# GEX_IDC_rev2.net
KiCad netlist of a schematic drawn in Altium Designer
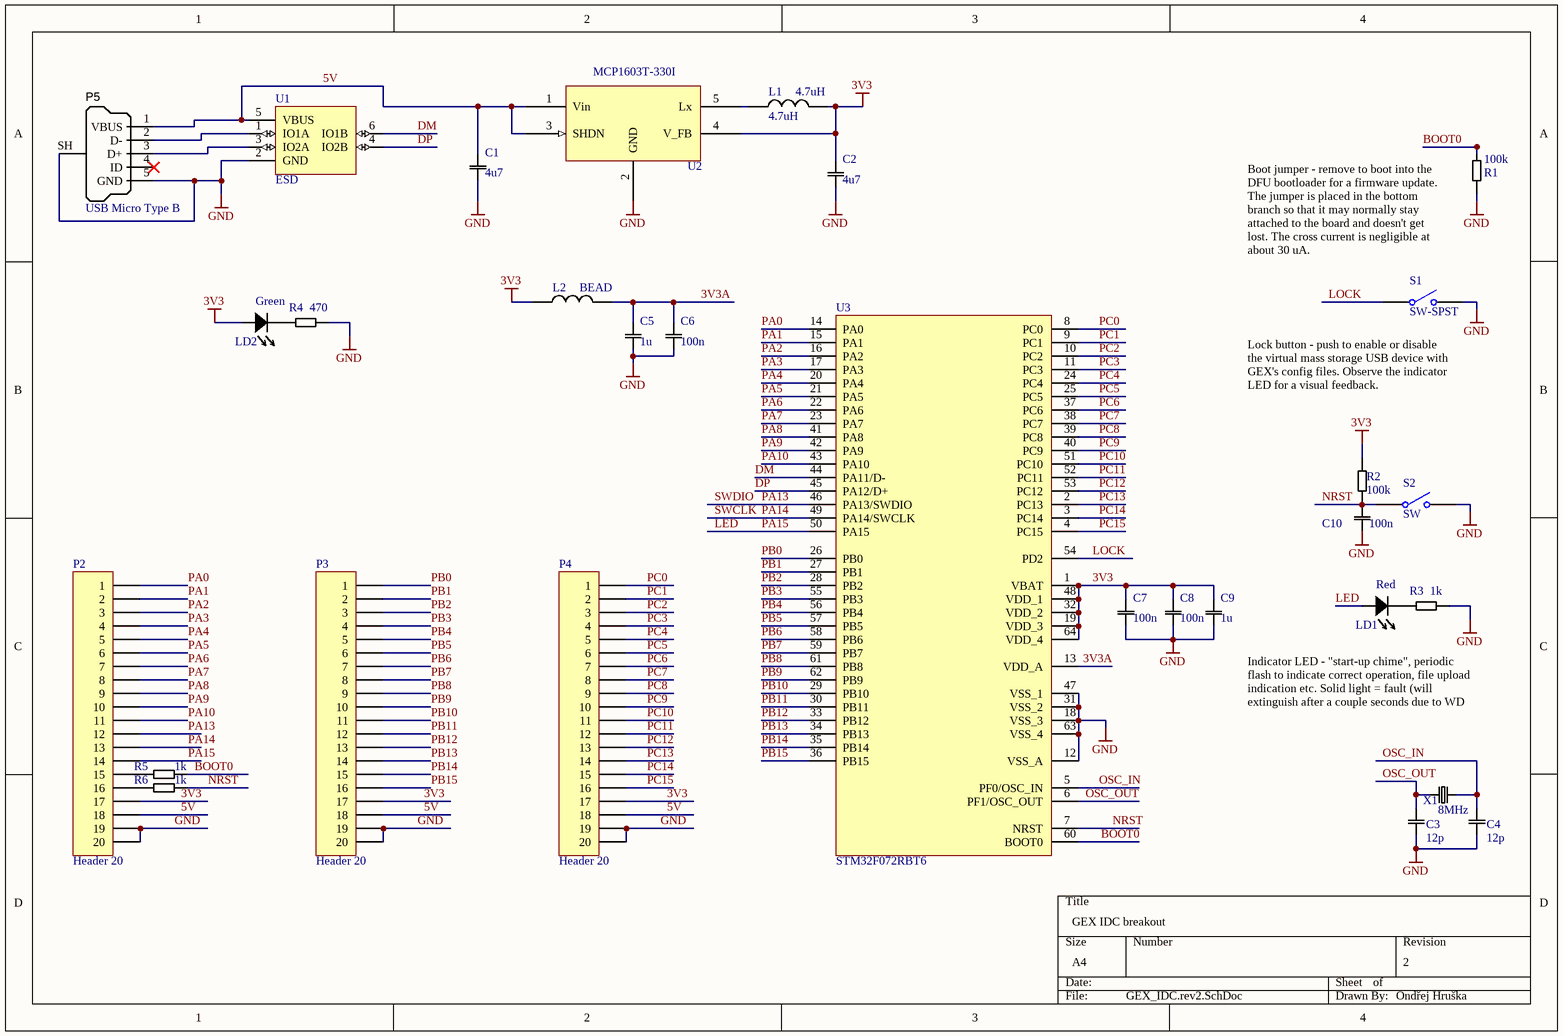
[diagram p0: GEX_IDC.rev2.SchDoc]

(export (version "E")
  (design (tool "Eeschema 10.0.6"))
  (components
    (comp (ref "C1")
      (value "4u7")
      (footprint "ABU_standard:C1206")
      (libsource (lib "ABU_standard") (part "C"))
    )
    (comp (ref "C2")
      (value "4u7")
      (footprint "ABU_standard:C1206")
      (libsource (lib "ABU_standard") (part "C"))
    )
    (comp (ref "C3")
      (value "12p")
      (footprint "ABU_standard:C0805")
      (libsource (lib "ABU_standard") (part "C"))
    )
    (comp (ref "C4")
      (value "12p")
      (footprint "ABU_standard:C0805")
      (libsource (lib "ABU_standard") (part "C"))
    )
    (comp (ref "C5")
      (value "1u")
      (footprint "ABU_standard:C0805")
      (libsource (lib "ABU_standard") (part "C"))
    )
    (comp (ref "C6")
      (value "100n")
      (footprint "ABU_standard:C0805")
      (libsource (lib "ABU_standard") (part "C"))
    )
    (comp (ref "C7")
      (value "100n")
      (footprint "ABU_standard:C0805")
      (libsource (lib "ABU_standard") (part "C"))
    )
    (comp (ref "C8")
      (value "100n")
      (footprint "ABU_standard:C0805")
      (libsource (lib "ABU_standard") (part "C"))
    )
    (comp (ref "C9")
      (value "1u")
      (footprint "ABU_standard:C0805")
      (libsource (lib "ABU_standard") (part "C"))
    )
    (comp (ref "C10")
      (value "100n")
      (footprint "ABU_standard:C0805")
      (libsource (lib "ABU_standard") (part "C"))
    )
    (comp (ref "L1")
      (value "4.7uH")
      (footprint "L_3x3")
      (description "Inductor")
      (fields (field (name "ALTIUM_VALUE") "4.7uH") (field (name "PART NUMBER") "VLS3015ET-4R7M"))
      (libsource (lib "ABU_standard") (part "L"))
    )
    (comp (ref "L2")
      (value "BEAD")
      (footprint "R0805")
      (description "Inductor")
      (libsource (lib "ABU_standard") (part "L"))
    )
    (comp (ref "LD1") (value "Red") (footprint "LED_SMD") (libsource (lib "ABU_standard") (part "LED")))
    (comp (ref "LD2") (value "Green") (footprint "LED_SMD") (libsource (lib "ABU_standard") (part "LED")))
    (comp (ref "P2")
      (value "Header 20")
      (footprint "MLW20_GEX_14")
      (description "Header, 20-Pin")
      (fields (field (name "PUBLISHER") "Altium Limited"))
      (libsource (lib "Miscellaneous Connectors") (part "Header 20"))
    )
    (comp (ref "P3")
      (value "Header 20")
      (footprint "MLW20_GEX_16")
      (description "Header, 20-Pin")
      (fields (field (name "PUBLISHER") "Altium Limited"))
      (libsource (lib "Miscellaneous Connectors") (part "Header 20"))
    )
    (comp (ref "P4")
      (value "Header 20")
      (footprint "MLW20_GEX_16")
      (description "Header, 20-Pin")
      (fields (field (name "PUBLISHER") "Altium Limited"))
      (libsource (lib "Miscellaneous Connectors") (part "Header 20"))
    )
    (comp (ref "P5")
      (value "USB Micro Type B")
      (footprint "USB_Micro-B_AFCI_10118194")
      (description "Connector SMD USB Micro Type B bottom mount, (recommended if hand soldering)")
      (fields (field (name "Comment") "USB_Micro_TypeB_Molex_105017"))
      (libsource (lib "CONN") (part "USB_Micro_TypeB_Molex_105017"))
    )
    (comp (ref "R1") (value "100k") (footprint "R0805") (libsource (lib "") (part "R_1")))
    (comp (ref "R2") (value "100k") (footprint "R0805") (libsource (lib "") (part "R_1")))
    (comp (ref "R3") (value "1k") (footprint "R0805") (libsource (lib "ABU_standard") (part "R")))
    (comp (ref "R4") (value "470") (footprint "R0805") (libsource (lib "ABU_standard") (part "R")))
    (comp (ref "R5") (value "1k") (footprint "R0805") (libsource (lib "ABU_standard") (part "R")))
    (comp (ref "R6") (value "1k") (footprint "R0805") (libsource (lib "ABU_standard") (part "R")))
    (comp (ref "S1")
      (value "SW-SPST")
      (footprint "BTN_AJ050")
      (description "Single-Pole, Single-Throw Switch")
      (fields (field (name "PUBLISHER") "Altium Limited"))
      (libsource (lib "Miscellaneous Devices") (part "SW-SPST"))
    )
    (comp (ref "S2") (value "SW") (footprint "SW_TINY_4PAD") (libsource (lib "CUSTOM") (part "SW_SPST_4PAD")))
    (comp (ref "U1") (value "ESD") (footprint "SOT23-6") (libsource (lib "CUSTOM") (part "USBLC6_ESD")))
    (comp (ref "U2")
      (value "MCP1603T-330I")
      (footprint "SOT23-5")
      (libsource (lib "CUSTOM") (part "MCP1603"))
    )
    (comp (ref "U3")
      (value "STM32F072RBT6")
      (footprint "LQFP64")
      (libsource (lib "CUSTOM") (part "STM32F072RBT6"))
    )
    (comp (ref "X1")
      (value "8MHz")
      (footprint "XTAL-SMD-50-32")
      (libsource (lib "ABU_standard") (part "XTALL"))
    )
  )
  (nets
    (net (code "1") (name "/3V3A") (class "Default")
      (node (ref "C5") (pin "2") (pinfunction "2_2") (pintype "passive"))
      (node (ref "C6") (pin "2") (pinfunction "2_2") (pintype "passive"))
      (node (ref "L2") (pin "2") (pinfunction "2_2") (pintype "passive"))
      (node (ref "U3") (pin "13") (pinfunction "VDD_A_13") (pintype "power_in"))
    )
    (net (code "2") (name "/5V") (class "Default")
      (node (ref "C1") (pin "2") (pinfunction "2_2") (pintype "passive"))
      (node (ref "P2") (pin "18") (pinfunction "18_18") (pintype "passive"))
      (node (ref "P3") (pin "18") (pinfunction "18_18") (pintype "passive"))
      (node (ref "P4") (pin "18") (pinfunction "18_18") (pintype "passive"))
      (node (ref "P5") (pin "1") (pinfunction "VBUS_1") (pintype "passive"))
      (node (ref "U1") (pin "5") (pinfunction "VBUS_5") (pintype "power_in"))
      (node (ref "U2") (pin "1") (pinfunction "Vin_1") (pintype "power_in"))
      (node (ref "U2") (pin "3") (pinfunction "SHDN_3") (pintype "input"))
    )
    (net (code "3") (name "/BOOT0") (class "Default")
      (node (ref "R1") (pin "1") (pinfunction "1_1") (pintype "passive"))
      (node (ref "R5") (pin "1") (pinfunction "1_1") (pintype "passive"))
      (node (ref "U3") (pin "60") (pinfunction "BOOT0_60") (pintype "passive"))
    )
    (net (code "4") (name "/DM") (class "Default")
      (node (ref "U1") (pin "6") (pinfunction "IO1B_6") (pintype "bidirectional"))
      (node (ref "U3") (pin "44") (pinfunction "PA11/D-_44") (pintype "passive"))
    )
    (net (code "5") (name "/DP") (class "Default")
      (node (ref "U1") (pin "4") (pinfunction "IO2B_4") (pintype "bidirectional"))
      (node (ref "U3") (pin "45") (pinfunction "PA12/D+_45") (pintype "passive"))
    )
    (net (code "6") (name "/LED") (class "Default")
      (node (ref "LD1") (pin "A") (pinfunction "A_A") (pintype "passive"))
      (node (ref "P2") (pin "14") (pinfunction "14_14") (pintype "passive"))
      (node (ref "U3") (pin "50") (pinfunction "PA15_50") (pintype "passive"))
    )
    (net (code "7") (name "/LOCK") (class "Default")
      (node (ref "S1") (pin "1") (pinfunction "COMMON_1") (pintype "passive"))
      (node (ref "U3") (pin "54") (pinfunction "PD2_54") (pintype "passive"))
    )
    (net (code "8") (name "/NRST") (class "Default")
      (node (ref "C10") (pin "2") (pinfunction "2_2") (pintype "passive"))
      (node (ref "R2") (pin "2") (pinfunction "2_2") (pintype "passive"))
      (node (ref "R6") (pin "1") (pinfunction "1_1") (pintype "passive"))
      (node (ref "S2") (pin "1") (pinfunction "COMMON_1") (pintype "passive"))
      (node (ref "U3") (pin "7") (pinfunction "NRST_7") (pintype "passive"))
    )
    (net (code "9") (name "/OSC_IN") (class "Default")
      (node (ref "C4") (pin "2") (pinfunction "2_2") (pintype "passive"))
      (node (ref "U3") (pin "5") (pinfunction "PF0/OSC_IN_5") (pintype "passive"))
      (node (ref "X1") (pin "2") (pinfunction "2_2") (pintype "passive"))
    )
    (net (code "10") (name "/OSC_OUT") (class "Default")
      (node (ref "C3") (pin "2") (pinfunction "2_2") (pintype "passive"))
      (node (ref "U3") (pin "6") (pinfunction "PF1/OSC_OUT_6") (pintype "passive"))
      (node (ref "X1") (pin "1") (pinfunction "1_1") (pintype "passive"))
    )
    (net (code "11") (name "/PA0") (class "Default")
      (node (ref "P2") (pin "1") (pinfunction "1_1") (pintype "passive"))
      (node (ref "U3") (pin "14") (pinfunction "PA0_14") (pintype "passive"))
    )
    (net (code "12") (name "/PA1") (class "Default")
      (node (ref "P2") (pin "2") (pinfunction "2_2") (pintype "passive"))
      (node (ref "U3") (pin "15") (pinfunction "PA1_15") (pintype "passive"))
    )
    (net (code "13") (name "/PA2") (class "Default")
      (node (ref "P2") (pin "3") (pinfunction "3_3") (pintype "passive"))
      (node (ref "U3") (pin "16") (pinfunction "PA2_16") (pintype "passive"))
    )
    (net (code "14") (name "/PA3") (class "Default")
      (node (ref "P2") (pin "4") (pinfunction "4_4") (pintype "passive"))
      (node (ref "U3") (pin "17") (pinfunction "PA3_17") (pintype "passive"))
    )
    (net (code "15") (name "/PA4") (class "Default")
      (node (ref "P2") (pin "5") (pinfunction "5_5") (pintype "passive"))
      (node (ref "U3") (pin "20") (pinfunction "PA4_20") (pintype "passive"))
    )
    (net (code "16") (name "/PA5") (class "Default")
      (node (ref "P2") (pin "6") (pinfunction "6_6") (pintype "passive"))
      (node (ref "U3") (pin "21") (pinfunction "PA5_21") (pintype "passive"))
    )
    (net (code "17") (name "/PA6") (class "Default")
      (node (ref "P2") (pin "7") (pinfunction "7_7") (pintype "passive"))
      (node (ref "U3") (pin "22") (pinfunction "PA6_22") (pintype "passive"))
    )
    (net (code "18") (name "/PA7") (class "Default")
      (node (ref "P2") (pin "8") (pinfunction "8_8") (pintype "passive"))
      (node (ref "U3") (pin "23") (pinfunction "PA7_23") (pintype "passive"))
    )
    (net (code "19") (name "/PA8") (class "Default")
      (node (ref "P2") (pin "9") (pinfunction "9_9") (pintype "passive"))
      (node (ref "U3") (pin "41") (pinfunction "PA8_41") (pintype "passive"))
    )
    (net (code "20") (name "/PA9") (class "Default")
      (node (ref "P2") (pin "10") (pinfunction "10_10") (pintype "passive"))
      (node (ref "U3") (pin "42") (pinfunction "PA9_42") (pintype "passive"))
    )
    (net (code "21") (name "/PA10") (class "Default")
      (node (ref "P2") (pin "11") (pinfunction "11_11") (pintype "passive"))
      (node (ref "U3") (pin "43") (pinfunction "PA10_43") (pintype "passive"))
    )
    (net (code "22") (name "/PA13") (class "Default")
      (node (ref "P2") (pin "12") (pinfunction "12_12") (pintype "passive"))
      (node (ref "U3") (pin "46") (pinfunction "PA13/SWDIO_46") (pintype "passive"))
    )
    (net (code "23") (name "/PA14") (class "Default")
      (node (ref "P2") (pin "13") (pinfunction "13_13") (pintype "passive"))
      (node (ref "U3") (pin "49") (pinfunction "PA14/SWCLK_49") (pintype "passive"))
    )
    (net (code "24") (name "/PB0") (class "Default")
      (node (ref "P3") (pin "1") (pinfunction "1_1") (pintype "passive"))
      (node (ref "U3") (pin "26") (pinfunction "PB0_26") (pintype "passive"))
    )
    (net (code "25") (name "/PB1") (class "Default")
      (node (ref "P3") (pin "2") (pinfunction "2_2") (pintype "passive"))
      (node (ref "U3") (pin "27") (pinfunction "PB1_27") (pintype "passive"))
    )
    (net (code "26") (name "/PB2") (class "Default")
      (node (ref "P3") (pin "3") (pinfunction "3_3") (pintype "passive"))
      (node (ref "U3") (pin "28") (pinfunction "PB2_28") (pintype "passive"))
    )
    (net (code "27") (name "/PB3") (class "Default")
      (node (ref "P3") (pin "4") (pinfunction "4_4") (pintype "passive"))
      (node (ref "U3") (pin "55") (pinfunction "PB3_55") (pintype "passive"))
    )
    (net (code "28") (name "/PB4") (class "Default")
      (node (ref "P3") (pin "5") (pinfunction "5_5") (pintype "passive"))
      (node (ref "U3") (pin "56") (pinfunction "PB4_56") (pintype "passive"))
    )
    (net (code "29") (name "/PB5") (class "Default")
      (node (ref "P3") (pin "6") (pinfunction "6_6") (pintype "passive"))
      (node (ref "U3") (pin "57") (pinfunction "PB5_57") (pintype "passive"))
    )
    (net (code "30") (name "/PB6") (class "Default")
      (node (ref "P3") (pin "7") (pinfunction "7_7") (pintype "passive"))
      (node (ref "U3") (pin "58") (pinfunction "PB6_58") (pintype "passive"))
    )
    (net (code "31") (name "/PB7") (class "Default")
      (node (ref "P3") (pin "8") (pinfunction "8_8") (pintype "passive"))
      (node (ref "U3") (pin "59") (pinfunction "PB7_59") (pintype "passive"))
    )
    (net (code "32") (name "/PB8") (class "Default")
      (node (ref "P3") (pin "9") (pinfunction "9_9") (pintype "passive"))
      (node (ref "U3") (pin "61") (pinfunction "PB8_61") (pintype "passive"))
    )
    (net (code "33") (name "/PB9") (class "Default")
      (node (ref "P3") (pin "10") (pinfunction "10_10") (pintype "passive"))
      (node (ref "U3") (pin "62") (pinfunction "PB9_62") (pintype "passive"))
    )
    (net (code "34") (name "/PB10") (class "Default")
      (node (ref "P3") (pin "11") (pinfunction "11_11") (pintype "passive"))
      (node (ref "U3") (pin "29") (pinfunction "PB10_29") (pintype "passive"))
    )
    (net (code "35") (name "/PB11") (class "Default")
      (node (ref "P3") (pin "12") (pinfunction "12_12") (pintype "passive"))
      (node (ref "U3") (pin "30") (pinfunction "PB11_30") (pintype "passive"))
    )
    (net (code "36") (name "/PB12") (class "Default")
      (node (ref "P3") (pin "13") (pinfunction "13_13") (pintype "passive"))
      (node (ref "U3") (pin "33") (pinfunction "PB12_33") (pintype "passive"))
    )
    (net (code "37") (name "/PB13") (class "Default")
      (node (ref "P3") (pin "14") (pinfunction "14_14") (pintype "passive"))
      (node (ref "U3") (pin "34") (pinfunction "PB13_34") (pintype "passive"))
    )
    (net (code "38") (name "/PB14") (class "Default")
      (node (ref "P3") (pin "15") (pinfunction "15_15") (pintype "passive"))
      (node (ref "U3") (pin "35") (pinfunction "PB14_35") (pintype "passive"))
    )
    (net (code "39") (name "/PB15") (class "Default")
      (node (ref "P3") (pin "16") (pinfunction "16_16") (pintype "passive"))
      (node (ref "U3") (pin "36") (pinfunction "PB15_36") (pintype "passive"))
    )
    (net (code "40") (name "/PC0") (class "Default")
      (node (ref "P4") (pin "1") (pinfunction "1_1") (pintype "passive"))
      (node (ref "U3") (pin "8") (pinfunction "PC0_8") (pintype "passive"))
    )
    (net (code "41") (name "/PC1") (class "Default")
      (node (ref "P4") (pin "2") (pinfunction "2_2") (pintype "passive"))
      (node (ref "U3") (pin "9") (pinfunction "PC1_9") (pintype "passive"))
    )
    (net (code "42") (name "/PC2") (class "Default")
      (node (ref "P4") (pin "3") (pinfunction "3_3") (pintype "passive"))
      (node (ref "U3") (pin "10") (pinfunction "PC2_10") (pintype "passive"))
    )
    (net (code "43") (name "/PC3") (class "Default")
      (node (ref "P4") (pin "4") (pinfunction "4_4") (pintype "passive"))
      (node (ref "U3") (pin "11") (pinfunction "PC3_11") (pintype "passive"))
    )
    (net (code "44") (name "/PC4") (class "Default")
      (node (ref "P4") (pin "5") (pinfunction "5_5") (pintype "passive"))
      (node (ref "U3") (pin "24") (pinfunction "PC4_24") (pintype "passive"))
    )
    (net (code "45") (name "/PC5") (class "Default")
      (node (ref "P4") (pin "6") (pinfunction "6_6") (pintype "passive"))
      (node (ref "U3") (pin "25") (pinfunction "PC5_25") (pintype "passive"))
    )
    (net (code "46") (name "/PC6") (class "Default")
      (node (ref "P4") (pin "7") (pinfunction "7_7") (pintype "passive"))
      (node (ref "U3") (pin "37") (pinfunction "PC6_37") (pintype "passive"))
    )
    (net (code "47") (name "/PC7") (class "Default")
      (node (ref "P4") (pin "8") (pinfunction "8_8") (pintype "passive"))
      (node (ref "U3") (pin "38") (pinfunction "PC7_38") (pintype "passive"))
    )
    (net (code "48") (name "/PC8") (class "Default")
      (node (ref "P4") (pin "9") (pinfunction "9_9") (pintype "passive"))
      (node (ref "U3") (pin "39") (pinfunction "PC8_39") (pintype "passive"))
    )
    (net (code "49") (name "/PC9") (class "Default")
      (node (ref "P4") (pin "10") (pinfunction "10_10") (pintype "passive"))
      (node (ref "U3") (pin "40") (pinfunction "PC9_40") (pintype "passive"))
    )
    (net (code "50") (name "/PC10") (class "Default")
      (node (ref "P4") (pin "11") (pinfunction "11_11") (pintype "passive"))
      (node (ref "U3") (pin "51") (pinfunction "PC10_51") (pintype "passive"))
    )
    (net (code "51") (name "/PC11") (class "Default")
      (node (ref "P4") (pin "12") (pinfunction "12_12") (pintype "passive"))
      (node (ref "U3") (pin "52") (pinfunction "PC11_52") (pintype "passive"))
    )
    (net (code "52") (name "/PC12") (class "Default")
      (node (ref "P4") (pin "13") (pinfunction "13_13") (pintype "passive"))
      (node (ref "U3") (pin "53") (pinfunction "PC12_53") (pintype "passive"))
    )
    (net (code "53") (name "/PC13") (class "Default")
      (node (ref "P4") (pin "14") (pinfunction "14_14") (pintype "passive"))
      (node (ref "U3") (pin "2") (pinfunction "PC13_2") (pintype "passive"))
    )
    (net (code "54") (name "/PC14") (class "Default")
      (node (ref "P4") (pin "15") (pinfunction "15_15") (pintype "passive"))
      (node (ref "U3") (pin "3") (pinfunction "PC14_3") (pintype "passive"))
    )
    (net (code "55") (name "/PC15") (class "Default")
      (node (ref "P4") (pin "16") (pinfunction "16_16") (pintype "passive"))
      (node (ref "U3") (pin "4") (pinfunction "PC15_4") (pintype "passive"))
    )
    (net (code "56") (name "3V3") (class "Default")
      (node (ref "C2") (pin "2") (pinfunction "2_2") (pintype "passive"))
      (node (ref "C7") (pin "2") (pinfunction "2_2") (pintype "passive"))
      (node (ref "C8") (pin "2") (pinfunction "2_2") (pintype "passive"))
      (node (ref "C9") (pin "2") (pinfunction "2_2") (pintype "passive"))
      (node (ref "L1") (pin "2") (pinfunction "2_2") (pintype "passive"))
      (node (ref "L2") (pin "1") (pinfunction "1_1") (pintype "passive"))
      (node (ref "LD2") (pin "A") (pinfunction "A_A") (pintype "passive"))
      (node (ref "P2") (pin "17") (pinfunction "17_17") (pintype "passive"))
      (node (ref "P3") (pin "17") (pinfunction "17_17") (pintype "passive"))
      (node (ref "P4") (pin "17") (pinfunction "17_17") (pintype "passive"))
      (node (ref "R2") (pin "1") (pinfunction "1_1") (pintype "passive"))
      (node (ref "U2") (pin "4") (pinfunction "V_FB_4") (pintype "passive"))
      (node (ref "U3") (pin "1") (pinfunction "VBAT_1") (pintype "passive"))
      (node (ref "U3") (pin "19") (pinfunction "VDD_3_19") (pintype "power_in"))
      (node (ref "U3") (pin "32") (pinfunction "VDD_2_32") (pintype "power_in"))
      (node (ref "U3") (pin "48") (pinfunction "VDD_1_48") (pintype "power_in"))
      (node (ref "U3") (pin "64") (pinfunction "VDD_4_64") (pintype "power_in"))
    )
    (net (code "57") (name "GND") (class "Default")
      (node (ref "C1") (pin "1") (pinfunction "1_1") (pintype "passive"))
      (node (ref "C10") (pin "1") (pinfunction "1_1") (pintype "passive"))
      (node (ref "C2") (pin "1") (pinfunction "1_1") (pintype "passive"))
      (node (ref "C3") (pin "1") (pinfunction "1_1") (pintype "passive"))
      (node (ref "C4") (pin "1") (pinfunction "1_1") (pintype "passive"))
      (node (ref "C5") (pin "1") (pinfunction "1_1") (pintype "passive"))
      (node (ref "C6") (pin "1") (pinfunction "1_1") (pintype "passive"))
      (node (ref "C7") (pin "1") (pinfunction "1_1") (pintype "passive"))
      (node (ref "C8") (pin "1") (pinfunction "1_1") (pintype "passive"))
      (node (ref "C9") (pin "1") (pinfunction "1_1") (pintype "passive"))
      (node (ref "P2") (pin "19") (pinfunction "19_19") (pintype "passive"))
      (node (ref "P2") (pin "20") (pinfunction "20_20") (pintype "passive"))
      (node (ref "P3") (pin "19") (pinfunction "19_19") (pintype "passive"))
      (node (ref "P3") (pin "20") (pinfunction "20_20") (pintype "passive"))
      (node (ref "P4") (pin "19") (pinfunction "19_19") (pintype "passive"))
      (node (ref "P4") (pin "20") (pinfunction "20_20") (pintype "passive"))
      (node (ref "P5") (pin "5") (pinfunction "GND_5") (pintype "passive"))
      (node (ref "P5") (pin "SH") (pinfunction "Shell_SH") (pintype "passive"))
      (node (ref "R1") (pin "2") (pinfunction "2_2") (pintype "passive"))
      (node (ref "R3") (pin "1") (pinfunction "1_1") (pintype "passive"))
      (node (ref "R4") (pin "1") (pinfunction "1_1") (pintype "passive"))
      (node (ref "S1") (pin "2") (pinfunction "NO_2") (pintype "passive"))
      (node (ref "S2") (pin "2") (pinfunction "NO_2") (pintype "passive"))
      (node (ref "U1") (pin "2") (pinfunction "GND_2") (pintype "power_in"))
      (node (ref "U2") (pin "2") (pinfunction "GND_2") (pintype "power_in"))
      (node (ref "U3") (pin "12") (pinfunction "VSS_A_12") (pintype "power_in"))
      (node (ref "U3") (pin "18") (pinfunction "VSS_3_18") (pintype "power_in"))
      (node (ref "U3") (pin "31") (pinfunction "VSS_2_31") (pintype "power_in"))
      (node (ref "U3") (pin "47") (pinfunction "VSS_1_47") (pintype "power_in"))
      (node (ref "U3") (pin "63") (pinfunction "VSS_4_63") (pintype "power_in"))
    )
    (net (code "58") (name "Net-(LD1-PadC)") (class "Default")
      (node (ref "LD1") (pin "C") (pinfunction "C_C") (pintype "passive"))
      (node (ref "R3") (pin "2") (pinfunction "2_2") (pintype "passive"))
    )
    (net (code "59") (name "Net-(LD2-PadC)") (class "Default")
      (node (ref "LD2") (pin "C") (pinfunction "C_C") (pintype "passive"))
      (node (ref "R4") (pin "2") (pinfunction "2_2") (pintype "passive"))
    )
    (net (code "60") (name "Net-(P2-Pad15)") (class "Default")
      (node (ref "P2") (pin "15") (pinfunction "15_15") (pintype "passive"))
      (node (ref "R5") (pin "2") (pinfunction "2_2") (pintype "passive"))
    )
    (net (code "61") (name "Net-(P2-Pad16)") (class "Default")
      (node (ref "P2") (pin "16") (pinfunction "16_16") (pintype "passive"))
      (node (ref "R6") (pin "2") (pinfunction "2_2") (pintype "passive"))
    )
    (net (code "62") (name "Net-(P5-D+)") (class "Default")
      (node (ref "P5") (pin "3") (pinfunction "D+_3") (pintype "passive"))
      (node (ref "U1") (pin "3") (pinfunction "IO2A_3") (pintype "bidirectional"))
    )
    (net (code "63") (name "Net-(P5-D-)") (class "Default")
      (node (ref "P5") (pin "2") (pinfunction "D-_2") (pintype "passive"))
      (node (ref "U1") (pin "1") (pinfunction "IO1A_1") (pintype "bidirectional"))
    )
    (net (code "64") (name "Net-(U2-Lx)") (class "Default")
      (node (ref "L1") (pin "1") (pinfunction "1_1") (pintype "passive"))
      (node (ref "U2") (pin "5") (pinfunction "Lx_5") (pintype "passive"))
    )
    (net (code "65") (name "unconnected-(P5-ID-Pad4)") (class "Default")
      (node (ref "P5") (pin "4") (pinfunction "ID_4") (pintype "passive+no_connect"))
    )
  )
)
